# 10.net
KiCad netlist of a schematic drawn in Altium Designer
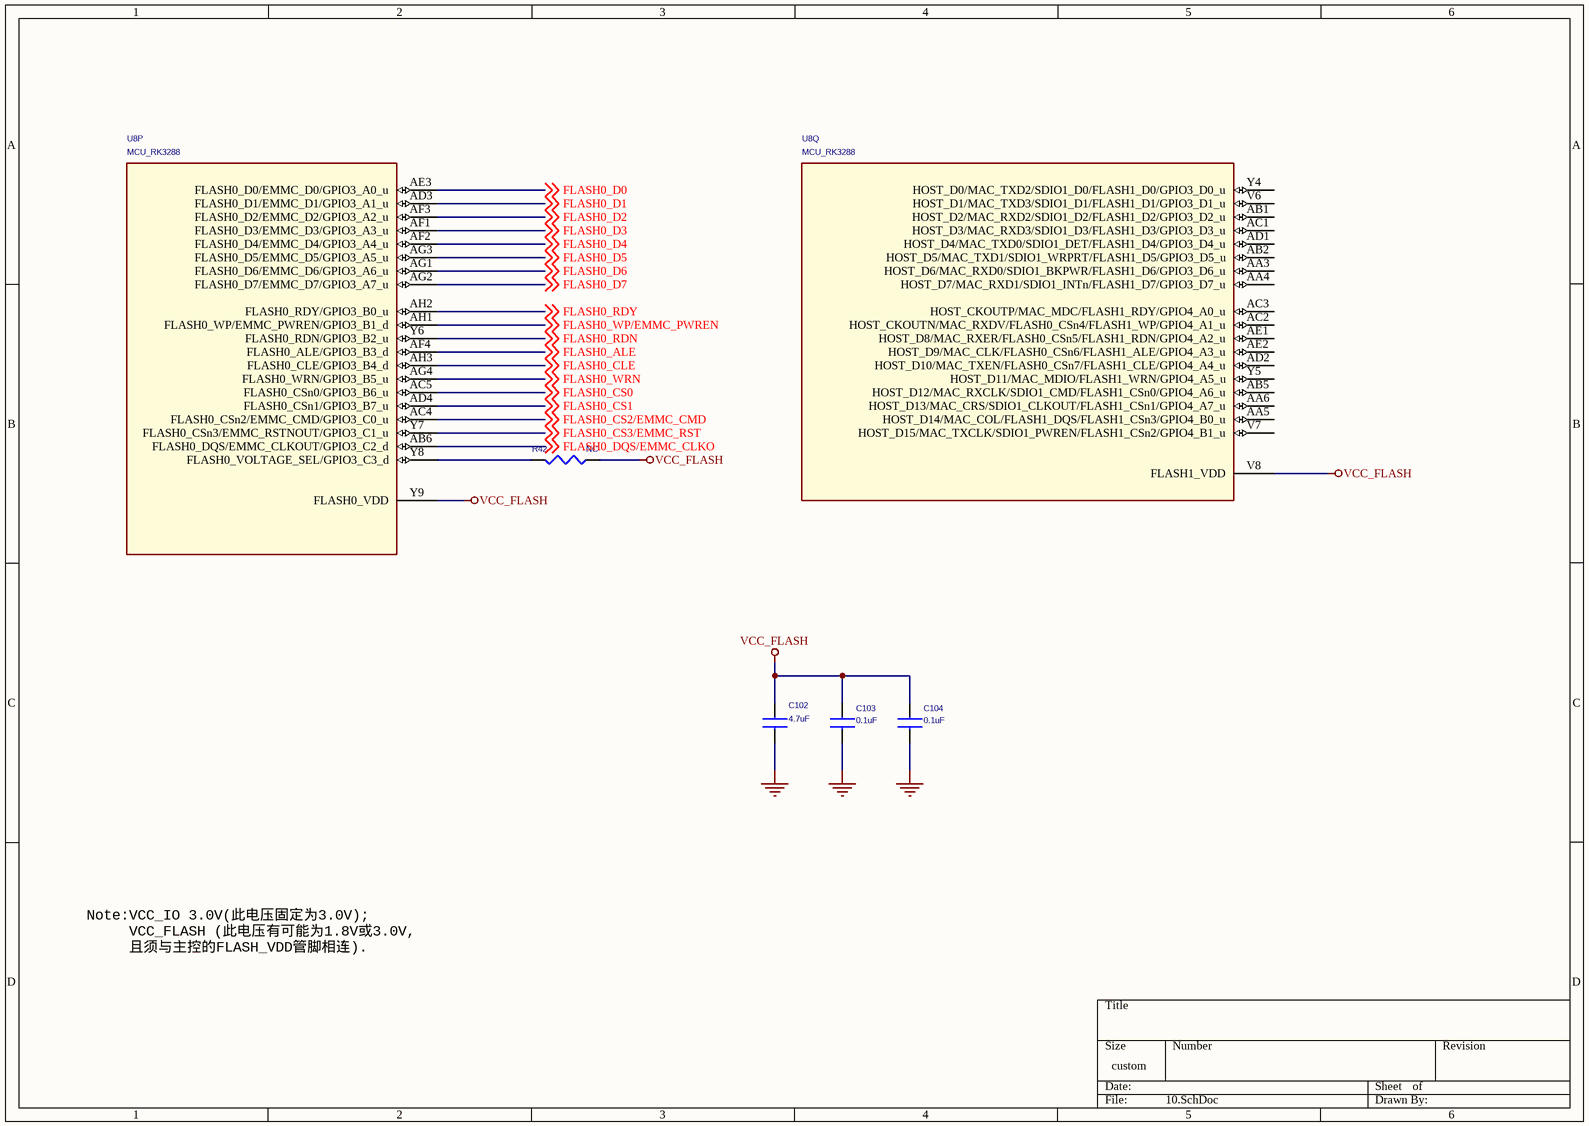
[diagram p0: 10.SchDoc]

(export (version "E")
  (design (tool "Eeschema 10.0.6"))
  (components
    (comp (ref "C102")
      (value "4.7uF")
      (footprint "C0603")
      (description "贴片电容")
      (libsource (lib "*") (part "CAP NP_Dup3"))
    )
    (comp (ref "C103")
      (value "0.1uF")
      (footprint "C0603")
      (description "RoHS CHIP CAP 0.1uF +10/-10% X7R")
      (libsource (lib "*") (part "CAP NP_Dup3"))
    )
    (comp (ref "C104")
      (value "0.1uF")
      (footprint "C0603")
      (description "RoHS CHIP CAP 0.1uF +10/-10% X7R")
      (libsource (lib "*") (part "CAP NP_Dup3"))
    )
    (comp (ref "R42") (value "NC") (footprint "r0402") (libsource (lib "*") (part "RESISTOR_1_Dup2")))
    (comp (ref "U8")
      (value "MCU_RK3288")
      (footprint "BGA453-19X19")
      (libsource (lib "*") (part "MCU_RK3288_3"))
    )
  )
  (nets
    (net (code "1") (name "FLASH0_ALE") (class "Default")
      (node (ref "U8") (pin "AF4") (pinfunction "FLASH0_ALE/GPIO3_B3_d_AF4") (pintype "bidirectional"))
    )
    (net (code "2") (name "FLASH0_CLE") (class "Default")
      (node (ref "U8") (pin "AH3") (pinfunction "FLASH0_CLE/GPIO3_B4_d_AH3") (pintype "bidirectional"))
    )
    (net (code "3") (name "FLASH0_CS0") (class "Default")
      (node (ref "U8") (pin "AC5") (pinfunction "FLASH0_CSn0/GPIO3_B6_u_AC5") (pintype "bidirectional"))
    )
    (net (code "4") (name "FLASH0_CS1") (class "Default")
      (node (ref "U8") (pin "AD4") (pinfunction "FLASH0_CSn1/GPIO3_B7_u_AD4") (pintype "bidirectional"))
    )
    (net (code "5") (name "FLASH0_CS2{slash}EMMC_CMD") (class "Default")
      (node (ref "U8") (pin "AC4") (pinfunction "FLASH0_CSn2/EMMC_CMD/GPIO3_C0_u_AC4") (pintype "bidirectional"))
    )
    (net (code "6") (name "FLASH0_CS3{slash}EMMC_RST") (class "Default")
      (node (ref "U8") (pin "Y7") (pinfunction "FLASH0_CSn3/EMMC_RSTNOUT/GPIO3_C1_u_Y7") (pintype "bidirectional"))
    )
    (net (code "7") (name "FLASH0_D0") (class "Default")
      (node (ref "U8") (pin "AE3") (pinfunction "FLASH0_D0/EMMC_D0/GPIO3_A0_u_AE3") (pintype "bidirectional"))
    )
    (net (code "8") (name "FLASH0_D1") (class "Default")
      (node (ref "U8") (pin "AD3") (pinfunction "FLASH0_D1/EMMC_D1/GPIO3_A1_u_AD3") (pintype "bidirectional"))
    )
    (net (code "9") (name "FLASH0_D2") (class "Default")
      (node (ref "U8") (pin "AF3") (pinfunction "FLASH0_D2/EMMC_D2/GPIO3_A2_u_AF3") (pintype "bidirectional"))
    )
    (net (code "10") (name "FLASH0_D3") (class "Default")
      (node (ref "U8") (pin "AF1") (pinfunction "FLASH0_D3/EMMC_D3/GPIO3_A3_u_AF1") (pintype "bidirectional"))
    )
    (net (code "11") (name "FLASH0_D4") (class "Default")
      (node (ref "U8") (pin "AF2") (pinfunction "FLASH0_D4/EMMC_D4/GPIO3_A4_u_AF2") (pintype "bidirectional"))
    )
    (net (code "12") (name "FLASH0_D5") (class "Default")
      (node (ref "U8") (pin "AG3") (pinfunction "FLASH0_D5/EMMC_D5/GPIO3_A5_u_AG3") (pintype "bidirectional"))
    )
    (net (code "13") (name "FLASH0_D6") (class "Default")
      (node (ref "U8") (pin "AG1") (pinfunction "FLASH0_D6/EMMC_D6/GPIO3_A6_u_AG1") (pintype "bidirectional"))
    )
    (net (code "14") (name "FLASH0_D7") (class "Default")
      (node (ref "U8") (pin "AG2") (pinfunction "FLASH0_D7/EMMC_D7/GPIO3_A7_u_AG2") (pintype "bidirectional"))
    )
    (net (code "15") (name "FLASH0_DQS{slash}EMMC_CLKO") (class "Default")
      (node (ref "U8") (pin "AB6") (pinfunction "FLASH0_DQS/EMMC_CLKOUT/GPIO3_C2_d_AB6") (pintype "bidirectional"))
    )
    (net (code "16") (name "FLASH0_RDN") (class "Default")
      (node (ref "U8") (pin "Y6") (pinfunction "FLASH0_RDN/GPIO3_B2_u_Y6") (pintype "bidirectional"))
    )
    (net (code "17") (name "FLASH0_RDY") (class "Default")
      (node (ref "U8") (pin "AH2") (pinfunction "FLASH0_RDY/GPIO3_B0_u_AH2") (pintype "bidirectional"))
    )
    (net (code "18") (name "FLASH0_WP{slash}EMMC_PWREN") (class "Default")
      (node (ref "U8") (pin "AH1") (pinfunction "FLASH0_WP/EMMC_PWREN/GPIO3_B1_d_AH1") (pintype "bidirectional"))
    )
    (net (code "19") (name "FLASH0_WRN") (class "Default")
      (node (ref "U8") (pin "AG4") (pinfunction "FLASH0_WRN/GPIO3_B5_u_AG4") (pintype "bidirectional"))
    )
    (net (code "20") (name "GND") (class "Default")
      (node (ref "C102") (pin "2") (pinfunction "2_2") (pintype "passive"))
      (node (ref "C103") (pin "2") (pinfunction "2_2") (pintype "passive"))
      (node (ref "C104") (pin "2") (pinfunction "2_2") (pintype "passive"))
    )
    (net (code "21") (name "Net-(U8P-FLASH0_VOLTAGE_SEL{slash}GPIO3_C3_d)") (class "Default")
      (node (ref "R42") (pin "2") (pinfunction "2_2") (pintype "passive"))
      (node (ref "U8") (pin "Y8") (pinfunction "FLASH0_VOLTAGE_SEL/GPIO3_C3_d_Y8") (pintype "bidirectional"))
    )
    (net (code "22") (name "VCC_FLASH") (class "Default")
      (node (ref "C102") (pin "1") (pinfunction "1_1") (pintype "passive"))
      (node (ref "C103") (pin "1") (pinfunction "1_1") (pintype "passive"))
      (node (ref "C104") (pin "1") (pinfunction "1_1") (pintype "passive"))
      (node (ref "R42") (pin "1") (pinfunction "1_1") (pintype "passive"))
      (node (ref "U8") (pin "V8") (pinfunction "FLASH1_VDD_V8") (pintype "power_in"))
      (node (ref "U8") (pin "Y9") (pinfunction "FLASH0_VDD_Y9") (pintype "power_in"))
    )
    (net (code "23") (name "unconnected-(U8Q-HOST_CKOUTN{slash}MAC_RXDV{slash}FLASH0_CSn4{slash}FLASH1_WP{slash}GPIO4_A1_u-PadAC2)") (class "Default")
      (node (ref "U8") (pin "AC2") (pinfunction "HOST_CKOUTN/MAC_RXDV/FLASH0_CSn4/FLASH1_WP/GPIO4_A1_u_AC2") (pintype "bidirectional"))
    )
    (net (code "24") (name "unconnected-(U8Q-HOST_CKOUTP{slash}MAC_MDC{slash}FLASH1_RDY{slash}GPIO4_A0_u-PadAC3)") (class "Default")
      (node (ref "U8") (pin "AC3") (pinfunction "HOST_CKOUTP/MAC_MDC/FLASH1_RDY/GPIO4_A0_u_AC3") (pintype "bidirectional"))
    )
    (net (code "25") (name "unconnected-(U8Q-HOST_D0{slash}MAC_TXD2{slash}SDIO1_D0{slash}FLASH1_D0{slash}GPIO3_D0_u-PadY4)") (class "Default")
      (node (ref "U8") (pin "Y4") (pinfunction "HOST_D0/MAC_TXD2/SDIO1_D0/FLASH1_D0/GPIO3_D0_u_Y4") (pintype "bidirectional"))
    )
    (net (code "26") (name "unconnected-(U8Q-HOST_D1{slash}MAC_TXD3{slash}SDIO1_D1{slash}FLASH1_D1{slash}GPIO3_D1_u-PadV6)") (class "Default")
      (node (ref "U8") (pin "V6") (pinfunction "HOST_D1/MAC_TXD3/SDIO1_D1/FLASH1_D1/GPIO3_D1_u_V6") (pintype "bidirectional"))
    )
    (net (code "27") (name "unconnected-(U8Q-HOST_D2{slash}MAC_RXD2{slash}SDIO1_D2{slash}FLASH1_D2{slash}GPIO3_D2_u-PadAB1)") (class "Default")
      (node (ref "U8") (pin "AB1") (pinfunction "HOST_D2/MAC_RXD2/SDIO1_D2/FLASH1_D2/GPIO3_D2_u_AB1") (pintype "bidirectional"))
    )
    (net (code "28") (name "unconnected-(U8Q-HOST_D3{slash}MAC_RXD3{slash}SDIO1_D3{slash}FLASH1_D3{slash}GPIO3_D3_u-PadAC1)") (class "Default")
      (node (ref "U8") (pin "AC1") (pinfunction "HOST_D3/MAC_RXD3/SDIO1_D3/FLASH1_D3/GPIO3_D3_u_AC1") (pintype "bidirectional"))
    )
    (net (code "29") (name "unconnected-(U8Q-HOST_D4{slash}MAC_TXD0{slash}SDIO1_DET{slash}FLASH1_D4{slash}GPIO3_D4_u-PadAD1)") (class "Default")
      (node (ref "U8") (pin "AD1") (pinfunction "HOST_D4/MAC_TXD0/SDIO1_DET/FLASH1_D4/GPIO3_D4_u_AD1") (pintype "bidirectional"))
    )
    (net (code "30") (name "unconnected-(U8Q-HOST_D5{slash}MAC_TXD1{slash}SDIO1_WRPRT{slash}FLASH1_D5{slash}GPIO3_D5_u-PadAB2)") (class "Default")
      (node (ref "U8") (pin "AB2") (pinfunction "HOST_D5/MAC_TXD1/SDIO1_WRPRT/FLASH1_D5/GPIO3_D5_u_AB2") (pintype "bidirectional"))
    )
    (net (code "31") (name "unconnected-(U8Q-HOST_D6{slash}MAC_RXD0{slash}SDIO1_BKPWR{slash}FLASH1_D6{slash}GPIO3_D6_u-PadAA3)") (class "Default")
      (node (ref "U8") (pin "AA3") (pinfunction "HOST_D6/MAC_RXD0/SDIO1_BKPWR/FLASH1_D6/GPIO3_D6_u_AA3") (pintype "bidirectional"))
    )
    (net (code "32") (name "unconnected-(U8Q-HOST_D7{slash}MAC_RXD1{slash}SDIO1_INTn{slash}FLASH1_D7{slash}GPIO3_D7_u-PadAA4)") (class "Default")
      (node (ref "U8") (pin "AA4") (pinfunction "HOST_D7/MAC_RXD1/SDIO1_INTn/FLASH1_D7/GPIO3_D7_u_AA4") (pintype "bidirectional"))
    )
    (net (code "33") (name "unconnected-(U8Q-HOST_D8{slash}MAC_RXER{slash}FLASH0_CSn5{slash}FLASH1_RDN{slash}GPIO4_A2_u-PadAE1)") (class "Default")
      (node (ref "U8") (pin "AE1") (pinfunction "HOST_D8/MAC_RXER/FLASH0_CSn5/FLASH1_RDN/GPIO4_A2_u_AE1") (pintype "bidirectional"))
    )
    (net (code "34") (name "unconnected-(U8Q-HOST_D9{slash}MAC_CLK{slash}FLASH0_CSn6{slash}FLASH1_ALE{slash}GPIO4_A3_u-PadAE2)") (class "Default")
      (node (ref "U8") (pin "AE2") (pinfunction "HOST_D9/MAC_CLK/FLASH0_CSn6/FLASH1_ALE/GPIO4_A3_u_AE2") (pintype "bidirectional"))
    )
    (net (code "35") (name "unconnected-(U8Q-HOST_D10{slash}MAC_TXEN{slash}FLASH0_CSn7{slash}FLASH1_CLE{slash}GPIO4_A4_u-PadAD2)") (class "Default")
      (node (ref "U8") (pin "AD2") (pinfunction "HOST_D10/MAC_TXEN/FLASH0_CSn7/FLASH1_CLE/GPIO4_A4_u_AD2") (pintype "bidirectional"))
    )
    (net (code "36") (name "unconnected-(U8Q-HOST_D11{slash}MAC_MDIO{slash}FLASH1_WRN{slash}GPIO4_A5_u-PadY5)") (class "Default")
      (node (ref "U8") (pin "Y5") (pinfunction "HOST_D11/MAC_MDIO/FLASH1_WRN/GPIO4_A5_u_Y5") (pintype "bidirectional"))
    )
    (net (code "37") (name "unconnected-(U8Q-HOST_D12{slash}MAC_RXCLK{slash}SDIO1_CMD{slash}FLASH1_CSn0{slash}GPIO4_A6_u-PadAB5)") (class "Default")
      (node (ref "U8") (pin "AB5") (pinfunction "HOST_D12/MAC_RXCLK/SDIO1_CMD/FLASH1_CSn0/GPIO4_A6_u_AB5") (pintype "bidirectional"))
    )
    (net (code "38") (name "unconnected-(U8Q-HOST_D13{slash}MAC_CRS{slash}SDIO1_CLKOUT{slash}FLASH1_CSn1{slash}GPIO4_A7_u-PadAA6)") (class "Default")
      (node (ref "U8") (pin "AA6") (pinfunction "HOST_D13/MAC_CRS/SDIO1_CLKOUT/FLASH1_CSn1/GPIO4_A7_u_AA6") (pintype "bidirectional"))
    )
    (net (code "39") (name "unconnected-(U8Q-HOST_D14{slash}MAC_COL{slash}FLASH1_DQS{slash}FLASH1_CSn3{slash}GPIO4_B0_u-PadAA5)") (class "Default")
      (node (ref "U8") (pin "AA5") (pinfunction "HOST_D14/MAC_COL/FLASH1_DQS/FLASH1_CSn3/GPIO4_B0_u_AA5") (pintype "bidirectional"))
    )
    (net (code "40") (name "unconnected-(U8Q-HOST_D15{slash}MAC_TXCLK{slash}SDIO1_PWREN{slash}FLASH1_CSn2{slash}GPIO4_B1_u-PadV7)") (class "Default")
      (node (ref "U8") (pin "V7") (pinfunction "HOST_D15/MAC_TXCLK/SDIO1_PWREN/FLASH1_CSn2/GPIO4_B1_u_V7") (pintype "bidirectional"))
    )
  )
)
